# ST_LINK.net
KiCad netlist of a schematic drawn in Altium Designer
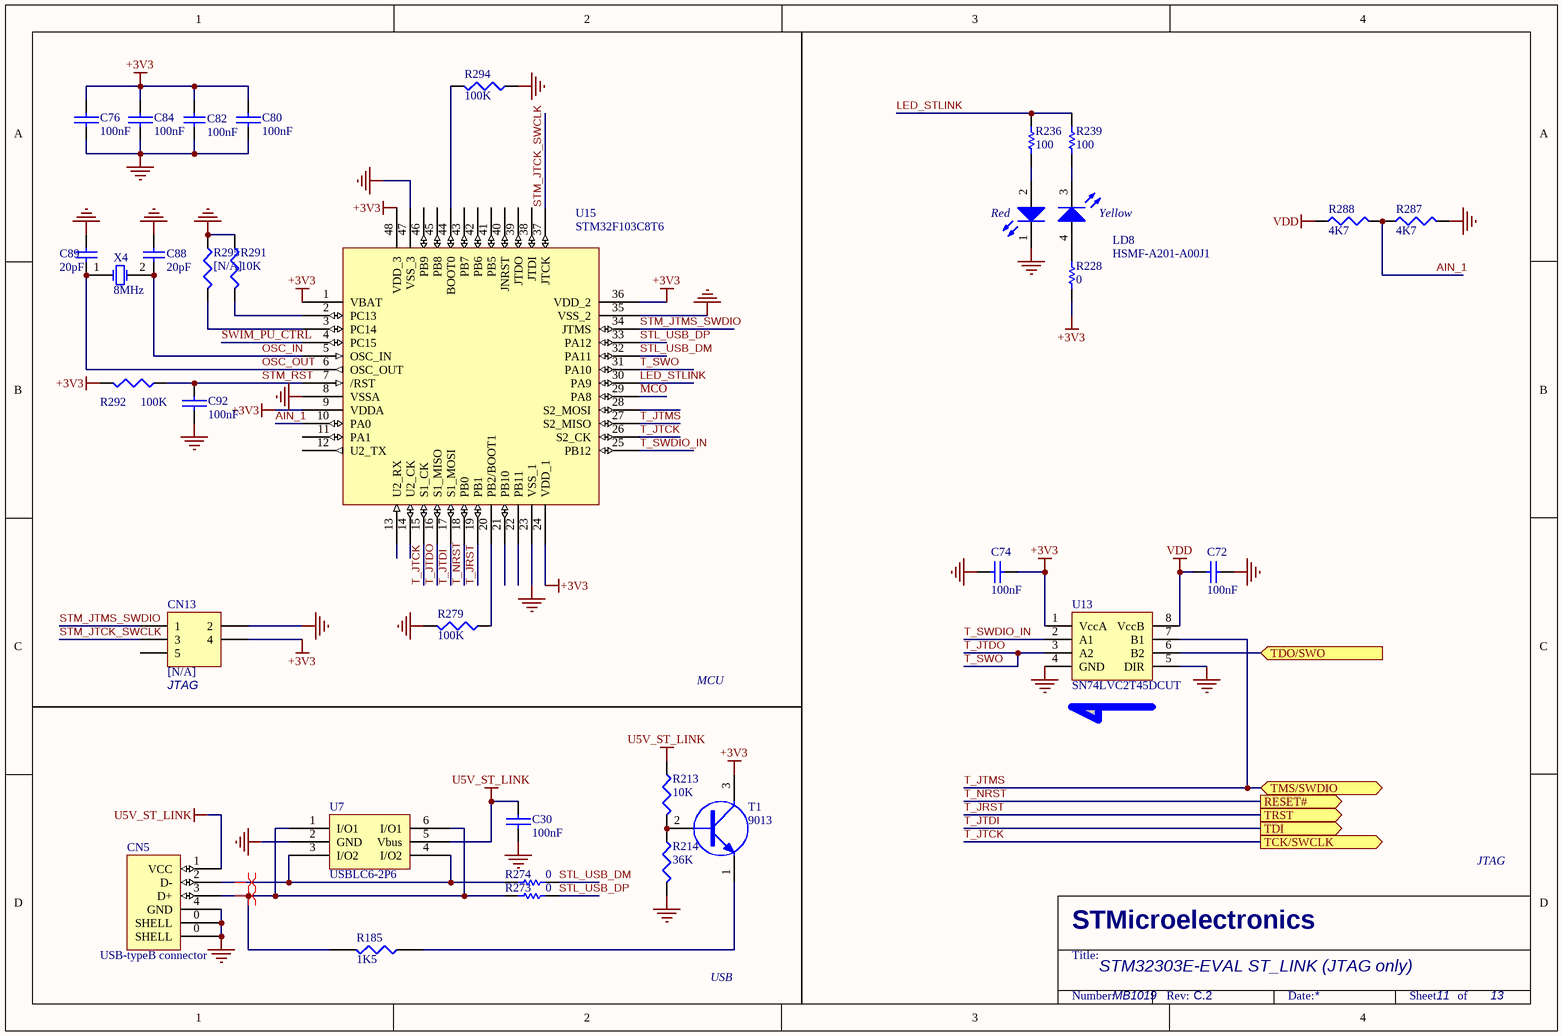
[diagram p0: ST_LINK.SCHDOC]

(export (version "E")
  (design (tool "Eeschema 10.0.6"))
  (components
    (comp (ref "C30")
      (value "100nF")
      (footprint "0603C")
      (description "Capacitor")
      (libsource (lib "") (part "CAP_1"))
    )
    (comp (ref "C72")
      (value "100nF")
      (footprint "0603C")
      (description "Capacitor")
      (fields (field (name "PUBLISHER") "Altium Limited"))
      (libsource (lib "Miscellaneous Devices") (part "CAP"))
    )
    (comp (ref "C74")
      (value "100nF")
      (footprint "0603C")
      (description "Capacitor")
      (fields (field (name "PUBLISHER") "Altium Limited"))
      (libsource (lib "Miscellaneous Devices") (part "CAP"))
    )
    (comp (ref "C76") (value "100nF") (footprint "0603C") (libsource (lib "*") (part "CAP")))
    (comp (ref "C80") (value "100nF") (footprint "0603C") (libsource (lib "*") (part "CAP")))
    (comp (ref "C82")
      (value "100nF")
      (footprint "0603C")
      (description "Capacitor")
      (fields (field (name "PUBLISHER") "Altium Limited"))
      (libsource (lib "*") (part "Cap"))
    )
    (comp (ref "C84") (value "100nF") (footprint "0603C") (libsource (lib "*") (part "CAP")))
    (comp (ref "C88")
      (value "20pF")
      (footprint "0603C")
      (description "Capacitor")
      (fields (field (name "PUBLISHER") "Altium Limited"))
      (libsource (lib "*") (part "Cap"))
    )
    (comp (ref "C89")
      (value "20pF")
      (footprint "0603C")
      (description "Capacitor")
      (fields (field (name "PUBLISHER") "Altium Limited"))
      (libsource (lib "*") (part "Cap"))
    )
    (comp (ref "C92") (value "100nF") (footprint "0603C") (libsource (lib "*") (part "CAP")))
    (comp (ref "CN5")
      (value "USB-typeB connector")
      (footprint "USB-B")
      (libsource (lib "*") (part "USB-typeB connector"))
    )
    (comp (ref "CN13")
      (value "[N/A]")
      (footprint "2*3P")
      (description "Header, 3-Pin, Dual row")
      (fields (field (name "PUBLISHER") "Altium Limited"))
      (libsource (lib "Miscellaneous Connectors") (part "Header 3X2"))
    )
    (comp (ref "LD8")
      (value "HSMF-A201-A00J1")
      (footprint "LED2-28*32")
      (libsource (lib "MB819") (part "HSMF-A201-A00J1"))
    )
    (comp (ref "R185") (value "1K5") (footprint "0603R") (libsource (lib "") (part "RES1_1")))
    (comp (ref "R213") (value "10K") (footprint "0603R") (libsource (lib "*") (part "R")))
    (comp (ref "R214") (value "36K") (footprint "0603R") (libsource (lib "*") (part "R")))
    (comp (ref "R228")
      (value "0")
      (footprint "0603R")
      (description "Resistor")
      (fields (field (name "PUBLISHER") "Altium Limited"))
      (libsource (lib "Miscellaneous Devices") (part "Res1"))
    )
    (comp (ref "R236")
      (value "100")
      (footprint "0603R")
      (description "Resistor")
      (fields (field (name "PUBLISHER") "Altium Limited"))
      (libsource (lib "Miscellaneous Devices") (part "Res1"))
    )
    (comp (ref "R239")
      (value "100")
      (footprint "0603R")
      (description "Resistor")
      (fields (field (name "PUBLISHER") "Altium Limited"))
      (libsource (lib "Miscellaneous Devices") (part "Res1"))
    )
    (comp (ref "R273")
      (value "0")
      (footprint "0603R")
      (description "Resistor")
      (fields (field (name "PUBLISHER") "Altium Limited"))
      (libsource (lib "Miscellaneous Devices") (part "Res1"))
    )
    (comp (ref "R274")
      (value "0")
      (footprint "0603R")
      (description "Resistor")
      (fields (field (name "PUBLISHER") "Altium Limited"))
      (libsource (lib "Miscellaneous Devices") (part "Res1"))
    )
    (comp (ref "R279") (value "100K") (footprint "0603R") (libsource (lib "*") (part "RES1")))
    (comp (ref "R287") (value "4K7") (footprint "0603R") (libsource (lib "*") (part "RES1")))
    (comp (ref "R288") (value "4K7") (footprint "0603R") (libsource (lib "*") (part "RES1")))
    (comp (ref "R291") (value "10K") (footprint "0603R") (libsource (lib "*") (part "R")))
    (comp (ref "R292") (value "100K") (footprint "0603R") (libsource (lib "*") (part "RES1")))
    (comp (ref "R294") (value "100K") (footprint "0603R") (libsource (lib "*") (part "RES1")))
    (comp (ref "R295") (value "[N/A]") (footprint "0603R") (libsource (lib "*") (part "R")))
    (comp (ref "T1") (value "9013") (footprint "SOT-23") (libsource (lib "*") (part "NPN")))
    (comp (ref "U7")
      (value "USBLC6-2P6")
      (footprint "SOT-666")
      (libsource (lib "STR910_SCHLIB") (part "USBLC6-2"))
    )
    (comp (ref "U13")
      (value "SN74LVC2T45DCUT")
      (footprint "VSSOP8")
      (libsource (lib "STLINK") (part "SN74LVC2T45DCUT"))
    )
    (comp (ref "U15")
      (value "STM32F103C8T6")
      (footprint "LQFP48")
      (libsource (lib "*") (part "STM32F10x(48pin)"))
    )
    (comp (ref "X4")
      (value "8MHz")
      (footprint "SMT_XTAL")
      (description "Crystal Oscillator")
      (fields (field (name "PUBLISHER") "Altium Limited"))
      (libsource (lib "*") (part "XTAL"))
    )
  )
  (nets
    (net (code "1") (name "+3V3") (class "Default")
      (node (ref "C74") (pin "2") (pinfunction "2_2") (pintype "passive"))
      (node (ref "C76") (pin "2") (pinfunction "2_2") (pintype "passive"))
      (node (ref "C80") (pin "2") (pinfunction "2_2") (pintype "passive"))
      (node (ref "C82") (pin "1") (pinfunction "1_1") (pintype "passive"))
      (node (ref "C84") (pin "2") (pinfunction "2_2") (pintype "passive"))
      (node (ref "CN13") (pin "4") (pinfunction "4_4") (pintype "passive"))
      (node (ref "R228") (pin "2") (pinfunction "2_2") (pintype "passive"))
      (node (ref "R292") (pin "2") (pinfunction "2_2") (pintype "passive"))
      (node (ref "T1") (pin "3") (pinfunction "C_3") (pintype "passive"))
      (node (ref "U13") (pin "1") (pinfunction "VccA_1") (pintype "passive"))
      (node (ref "U15") (pin "1") (pinfunction "VBAT_1") (pintype "power_in"))
      (node (ref "U15") (pin "24") (pinfunction "VDD_1_24") (pintype "power_in"))
      (node (ref "U15") (pin "36") (pinfunction "VDD_2_36") (pintype "power_in"))
      (node (ref "U15") (pin "48") (pinfunction "VDD_3_48") (pintype "power_in"))
      (node (ref "U15") (pin "9") (pinfunction "VDDA_9") (pintype "power_in"))
    )
    (net (code "2") (name "/AIN_1") (class "Default")
      (node (ref "R287") (pin "1") (pinfunction "1_1") (pintype "passive"))
      (node (ref "R288") (pin "2") (pinfunction "2_2") (pintype "passive"))
      (node (ref "U15") (pin "10") (pinfunction "PA0_10") (pintype "bidirectional"))
    )
    (net (code "3") (name "/LED_STLINK") (class "Default")
      (node (ref "R236") (pin "1") (pinfunction "1_1") (pintype "passive"))
      (node (ref "R239") (pin "1") (pinfunction "1_1") (pintype "passive"))
      (node (ref "U15") (pin "30") (pinfunction "PA9_30") (pintype "bidirectional"))
    )
    (net (code "4") (name "/MCO") (class "Default")
      (node (ref "U15") (pin "29") (pinfunction "PA8_29") (pintype "bidirectional"))
    )
    (net (code "5") (name "/OSC_IN") (class "Default")
      (node (ref "C88") (pin "2") (pinfunction "2_2") (pintype "passive"))
      (node (ref "U15") (pin "5") (pinfunction "OSC_IN_5") (pintype "input"))
      (node (ref "X4") (pin "2") (pinfunction "OSC2_2") (pintype "passive"))
    )
    (net (code "6") (name "/OSC_OUT") (class "Default")
      (node (ref "C89") (pin "2") (pinfunction "2_2") (pintype "passive"))
      (node (ref "U15") (pin "6") (pinfunction "OSC_OUT_6") (pintype "output"))
      (node (ref "X4") (pin "1") (pinfunction "OSC1_1") (pintype "passive"))
    )
    (net (code "7") (name "/STL_USB_DM") (class "Default")
      (node (ref "R274") (pin "1") (pinfunction "1_1") (pintype "passive"))
      (node (ref "U15") (pin "32") (pinfunction "PA11_32") (pintype "bidirectional"))
    )
    (net (code "8") (name "/STL_USB_DP") (class "Default")
      (node (ref "R273") (pin "1") (pinfunction "1_1") (pintype "passive"))
      (node (ref "U15") (pin "33") (pinfunction "PA12_33") (pintype "bidirectional"))
    )
    (net (code "9") (name "/STM_JTCK_SWCLK") (class "Default")
      (node (ref "CN13") (pin "3") (pinfunction "3_3") (pintype "passive"))
      (node (ref "U15") (pin "37") (pinfunction "JTCK_37") (pintype "bidirectional"))
    )
    (net (code "10") (name "/STM_JTMS_SWDIO") (class "Default")
      (node (ref "CN13") (pin "1") (pinfunction "1_1") (pintype "passive"))
      (node (ref "U15") (pin "34") (pinfunction "JTMS_34") (pintype "bidirectional"))
    )
    (net (code "11") (name "/STM_RST") (class "Default")
      (node (ref "C92") (pin "2") (pinfunction "2_2") (pintype "passive"))
      (node (ref "R292") (pin "1") (pinfunction "1_1") (pintype "passive"))
      (node (ref "U15") (pin "7") (pinfunction "/RST_7") (pintype "input"))
    )
    (net (code "12") (name "/SWIM_PU_CTRL") (class "Default")
      (node (ref "U15") (pin "4") (pinfunction "PC15_4") (pintype "bidirectional"))
    )
    (net (code "13") (name "/TDO{slash}SWO") (class "Default")
      (node (ref "U13") (pin "6") (pinfunction "B2_6") (pintype "passive"))
    )
    (net (code "14") (name "/T_JRST") (class "Default")
      (node (ref "U15") (pin "19") (pinfunction "PB1_19") (pintype "bidirectional"))
    )
    (net (code "15") (name "/T_JTCK") (class "Default")
      (node (ref "U15") (pin "15") (pinfunction "S1_CK_15") (pintype "bidirectional"))
      (node (ref "U15") (pin "26") (pinfunction "S2_CK_26") (pintype "bidirectional"))
    )
    (net (code "16") (name "/T_JTDI") (class "Default")
      (node (ref "U15") (pin "17") (pinfunction "S1_MOSI_17") (pintype "bidirectional"))
    )
    (net (code "17") (name "/T_JTDO") (class "Default")
      (node (ref "U13") (pin "3") (pinfunction "A2_3") (pintype "passive"))
      (node (ref "U15") (pin "16") (pinfunction "S1_MISO_16") (pintype "bidirectional"))
      (node (ref "U15") (pin "31") (pinfunction "PA10_31") (pintype "bidirectional"))
    )
    (net (code "18") (name "/T_JTMS") (class "Default")
      (node (ref "U13") (pin "7") (pinfunction "B1_7") (pintype "passive"))
      (node (ref "U15") (pin "27") (pinfunction "S2_MISO_27") (pintype "bidirectional"))
    )
    (net (code "19") (name "/T_NRST") (class "Default")
      (node (ref "U15") (pin "18") (pinfunction "PB0_18") (pintype "bidirectional"))
    )
    (net (code "20") (name "/T_SWDIO_IN") (class "Default")
      (node (ref "U13") (pin "2") (pinfunction "A1_2") (pintype "passive"))
      (node (ref "U15") (pin "25") (pinfunction "PB12_25") (pintype "bidirectional"))
    )
    (net (code "21") (name "GND") (class "Default")
      (node (ref "C30") (pin "2") (pinfunction "2_2") (pintype "passive"))
      (node (ref "C72") (pin "2") (pinfunction "2_2") (pintype "passive"))
      (node (ref "C74") (pin "1") (pinfunction "1_1") (pintype "passive"))
      (node (ref "C76") (pin "1") (pinfunction "1_1") (pintype "passive"))
      (node (ref "C80") (pin "1") (pinfunction "1_1") (pintype "passive"))
      (node (ref "C82") (pin "2") (pinfunction "2_2") (pintype "passive"))
      (node (ref "C84") (pin "1") (pinfunction "1_1") (pintype "passive"))
      (node (ref "C88") (pin "1") (pinfunction "1_1") (pintype "passive"))
      (node (ref "C89") (pin "1") (pinfunction "1_1") (pintype "passive"))
      (node (ref "C92") (pin "1") (pinfunction "1_1") (pintype "passive"))
      (node (ref "CN13") (pin "2") (pinfunction "2_2") (pintype "passive"))
      (node (ref "CN5") (pin "0") (pinfunction "SHELL_0") (pintype "power_in"))
      (node (ref "CN5") (pin "4") (pinfunction "GND_4") (pintype "passive"))
      (node (ref "LD8") (pin "1") (pinfunction "RED_cathode_1") (pintype "passive"))
      (node (ref "R214") (pin "2") (pinfunction "2_2") (pintype "passive"))
      (node (ref "R279") (pin "2") (pinfunction "2_2") (pintype "passive"))
      (node (ref "R287") (pin "2") (pinfunction "2_2") (pintype "passive"))
      (node (ref "R291") (pin "1") (pinfunction "1_1") (pintype "passive"))
      (node (ref "R294") (pin "1") (pinfunction "1_1") (pintype "passive"))
      (node (ref "R295") (pin "1") (pinfunction "1_1") (pintype "passive"))
      (node (ref "U13") (pin "4") (pinfunction "GND_4") (pintype "passive"))
      (node (ref "U13") (pin "5") (pinfunction "DIR_5") (pintype "passive"))
      (node (ref "U15") (pin "23") (pinfunction "VSS_1_23") (pintype "passive"))
      (node (ref "U15") (pin "35") (pinfunction "VSS_2_35") (pintype "passive"))
      (node (ref "U15") (pin "47") (pinfunction "VSS_3_47") (pintype "passive"))
      (node (ref "U15") (pin "8") (pinfunction "VSSA_8") (pintype "passive"))
      (node (ref "U7") (pin "2") (pinfunction "GND_2") (pintype "passive"))
    )
    (net (code "22") (name "Net-(CN5-D+)") (class "Default")
      (node (ref "CN5") (pin "3") (pinfunction "D+_3") (pintype "bidirectional"))
      (node (ref "R185") (pin "2") (pinfunction "2_2") (pintype "passive"))
      (node (ref "R273") (pin "2") (pinfunction "2_2") (pintype "passive"))
      (node (ref "U7") (pin "1") (pinfunction "I/O1_1") (pintype "passive"))
      (node (ref "U7") (pin "6") (pinfunction "I/O1_6") (pintype "passive"))
    )
    (net (code "23") (name "Net-(CN5-D-)") (class "Default")
      (node (ref "CN5") (pin "2") (pinfunction "D-_2") (pintype "bidirectional"))
      (node (ref "R274") (pin "2") (pinfunction "2_2") (pintype "passive"))
      (node (ref "U7") (pin "3") (pinfunction "I/O2_3") (pintype "passive"))
      (node (ref "U7") (pin "4") (pinfunction "I/O2_4") (pintype "passive"))
    )
    (net (code "24") (name "Net-(LD8-Red_anode)") (class "Default")
      (node (ref "LD8") (pin "2") (pinfunction "Red_anode_2") (pintype "passive"))
      (node (ref "R236") (pin "2") (pinfunction "2_2") (pintype "passive"))
    )
    (net (code "25") (name "Net-(LD8-YellowGreen_anode)") (class "Default")
      (node (ref "LD8") (pin "4") (pinfunction "YellowGreen_anode_4") (pintype "passive"))
      (node (ref "R228") (pin "1") (pinfunction "1_1") (pintype "passive"))
    )
    (net (code "26") (name "Net-(LD8-YellowGreen_cathode)") (class "Default")
      (node (ref "LD8") (pin "3") (pinfunction "YellowGreen_cathode_3") (pintype "passive"))
      (node (ref "R239") (pin "2") (pinfunction "2_2") (pintype "passive"))
    )
    (net (code "27") (name "Net-(T1-B)") (class "Default")
      (node (ref "R213") (pin "2") (pinfunction "2_2") (pintype "passive"))
      (node (ref "R214") (pin "1") (pinfunction "1_1") (pintype "passive"))
      (node (ref "T1") (pin "2") (pinfunction "B_2") (pintype "passive"))
    )
    (net (code "28") (name "Net-(T1-E)") (class "Default")
      (node (ref "R185") (pin "1") (pinfunction "1_1") (pintype "passive"))
      (node (ref "T1") (pin "1") (pinfunction "E_1") (pintype "passive"))
    )
    (net (code "29") (name "Net-(U15-BOOT0)") (class "Default")
      (node (ref "R294") (pin "2") (pinfunction "2_2") (pintype "passive"))
      (node (ref "U15") (pin "44") (pinfunction "BOOT0_44") (pintype "bidirectional"))
    )
    (net (code "30") (name "Net-(U15-PB2{slash}BOOT1)") (class "Default")
      (node (ref "R279") (pin "1") (pinfunction "1_1") (pintype "passive"))
      (node (ref "U15") (pin "20") (pinfunction "PB2/BOOT1_20") (pintype "passive"))
    )
    (net (code "31") (name "Net-(U15-PC13)") (class "Default")
      (node (ref "R291") (pin "2") (pinfunction "2_2") (pintype "passive"))
      (node (ref "U15") (pin "2") (pinfunction "PC13_2") (pintype "bidirectional"))
    )
    (net (code "32") (name "Net-(U15-PC14)") (class "Default")
      (node (ref "R295") (pin "2") (pinfunction "2_2") (pintype "passive"))
      (node (ref "U15") (pin "3") (pinfunction "PC14_3") (pintype "bidirectional"))
    )
    (net (code "33") (name "U5V_ST_LINK") (class "Default")
      (node (ref "C30") (pin "1") (pinfunction "1_1") (pintype "passive"))
      (node (ref "CN5") (pin "1") (pinfunction "VCC_1") (pintype "bidirectional"))
      (node (ref "R213") (pin "1") (pinfunction "1_1") (pintype "passive"))
      (node (ref "U7") (pin "5") (pinfunction "Vbus_5") (pintype "passive"))
    )
    (net (code "34") (name "VDD") (class "Default")
      (node (ref "C72") (pin "1") (pinfunction "1_1") (pintype "passive"))
      (node (ref "R288") (pin "1") (pinfunction "1_1") (pintype "passive"))
      (node (ref "U13") (pin "8") (pinfunction "VccB_8") (pintype "passive"))
    )
    (net (code "35") (name "unconnected-(CN13-Pad5)") (class "Default")
      (node (ref "CN13") (pin "5") (pinfunction "5_5") (pintype "passive"))
    )
    (net (code "36") (name "unconnected-(U15-JNRST-Pad40)") (class "Default")
      (node (ref "U15") (pin "40") (pinfunction "JNRST_40") (pintype "bidirectional"))
    )
    (net (code "37") (name "unconnected-(U15-JTDI-Pad38)") (class "Default")
      (node (ref "U15") (pin "38") (pinfunction "JTDI_38") (pintype "bidirectional"))
    )
    (net (code "38") (name "unconnected-(U15-JTDO-Pad39)") (class "Default")
      (node (ref "U15") (pin "39") (pinfunction "JTDO_39") (pintype "bidirectional"))
    )
    (net (code "39") (name "unconnected-(U15-PA1-Pad11)") (class "Default")
      (node (ref "U15") (pin "11") (pinfunction "PA1_11") (pintype "bidirectional"))
    )
    (net (code "40") (name "unconnected-(U15-PB5-Pad41)") (class "Default")
      (node (ref "U15") (pin "41") (pinfunction "PB5_41") (pintype "bidirectional"))
    )
    (net (code "41") (name "unconnected-(U15-PB6-Pad42)") (class "Default")
      (node (ref "U15") (pin "42") (pinfunction "PB6_42") (pintype "bidirectional"))
    )
    (net (code "42") (name "unconnected-(U15-PB7-Pad43)") (class "Default")
      (node (ref "U15") (pin "43") (pinfunction "PB7_43") (pintype "bidirectional"))
    )
    (net (code "43") (name "unconnected-(U15-PB8-Pad45)") (class "Default")
      (node (ref "U15") (pin "45") (pinfunction "PB8_45") (pintype "bidirectional"))
    )
    (net (code "44") (name "unconnected-(U15-PB9-Pad46)") (class "Default")
      (node (ref "U15") (pin "46") (pinfunction "PB9_46") (pintype "bidirectional"))
    )
    (net (code "45") (name "unconnected-(U15-PB10-Pad21)") (class "Default")
      (node (ref "U15") (pin "21") (pinfunction "PB10_21") (pintype "bidirectional"))
    )
    (net (code "46") (name "unconnected-(U15-PB11-Pad22)") (class "Default")
      (node (ref "U15") (pin "22") (pinfunction "PB11_22") (pintype "passive"))
    )
    (net (code "47") (name "unconnected-(U15-S2_MOSI-Pad28)") (class "Default")
      (node (ref "U15") (pin "28") (pinfunction "S2_MOSI_28") (pintype "bidirectional"))
    )
    (net (code "48") (name "unconnected-(U15-U2_CK-Pad14)") (class "Default")
      (node (ref "U15") (pin "14") (pinfunction "U2_CK_14") (pintype "bidirectional"))
    )
    (net (code "49") (name "unconnected-(U15-U2_RX-Pad13)") (class "Default")
      (node (ref "U15") (pin "13") (pinfunction "U2_RX_13") (pintype "input"))
    )
    (net (code "50") (name "unconnected-(U15-U2_TX-Pad12)") (class "Default")
      (node (ref "U15") (pin "12") (pinfunction "U2_TX_12") (pintype "output"))
    )
  )
)
